# schema.net
KiCad netlist of a schematic drawn in Altium Designer
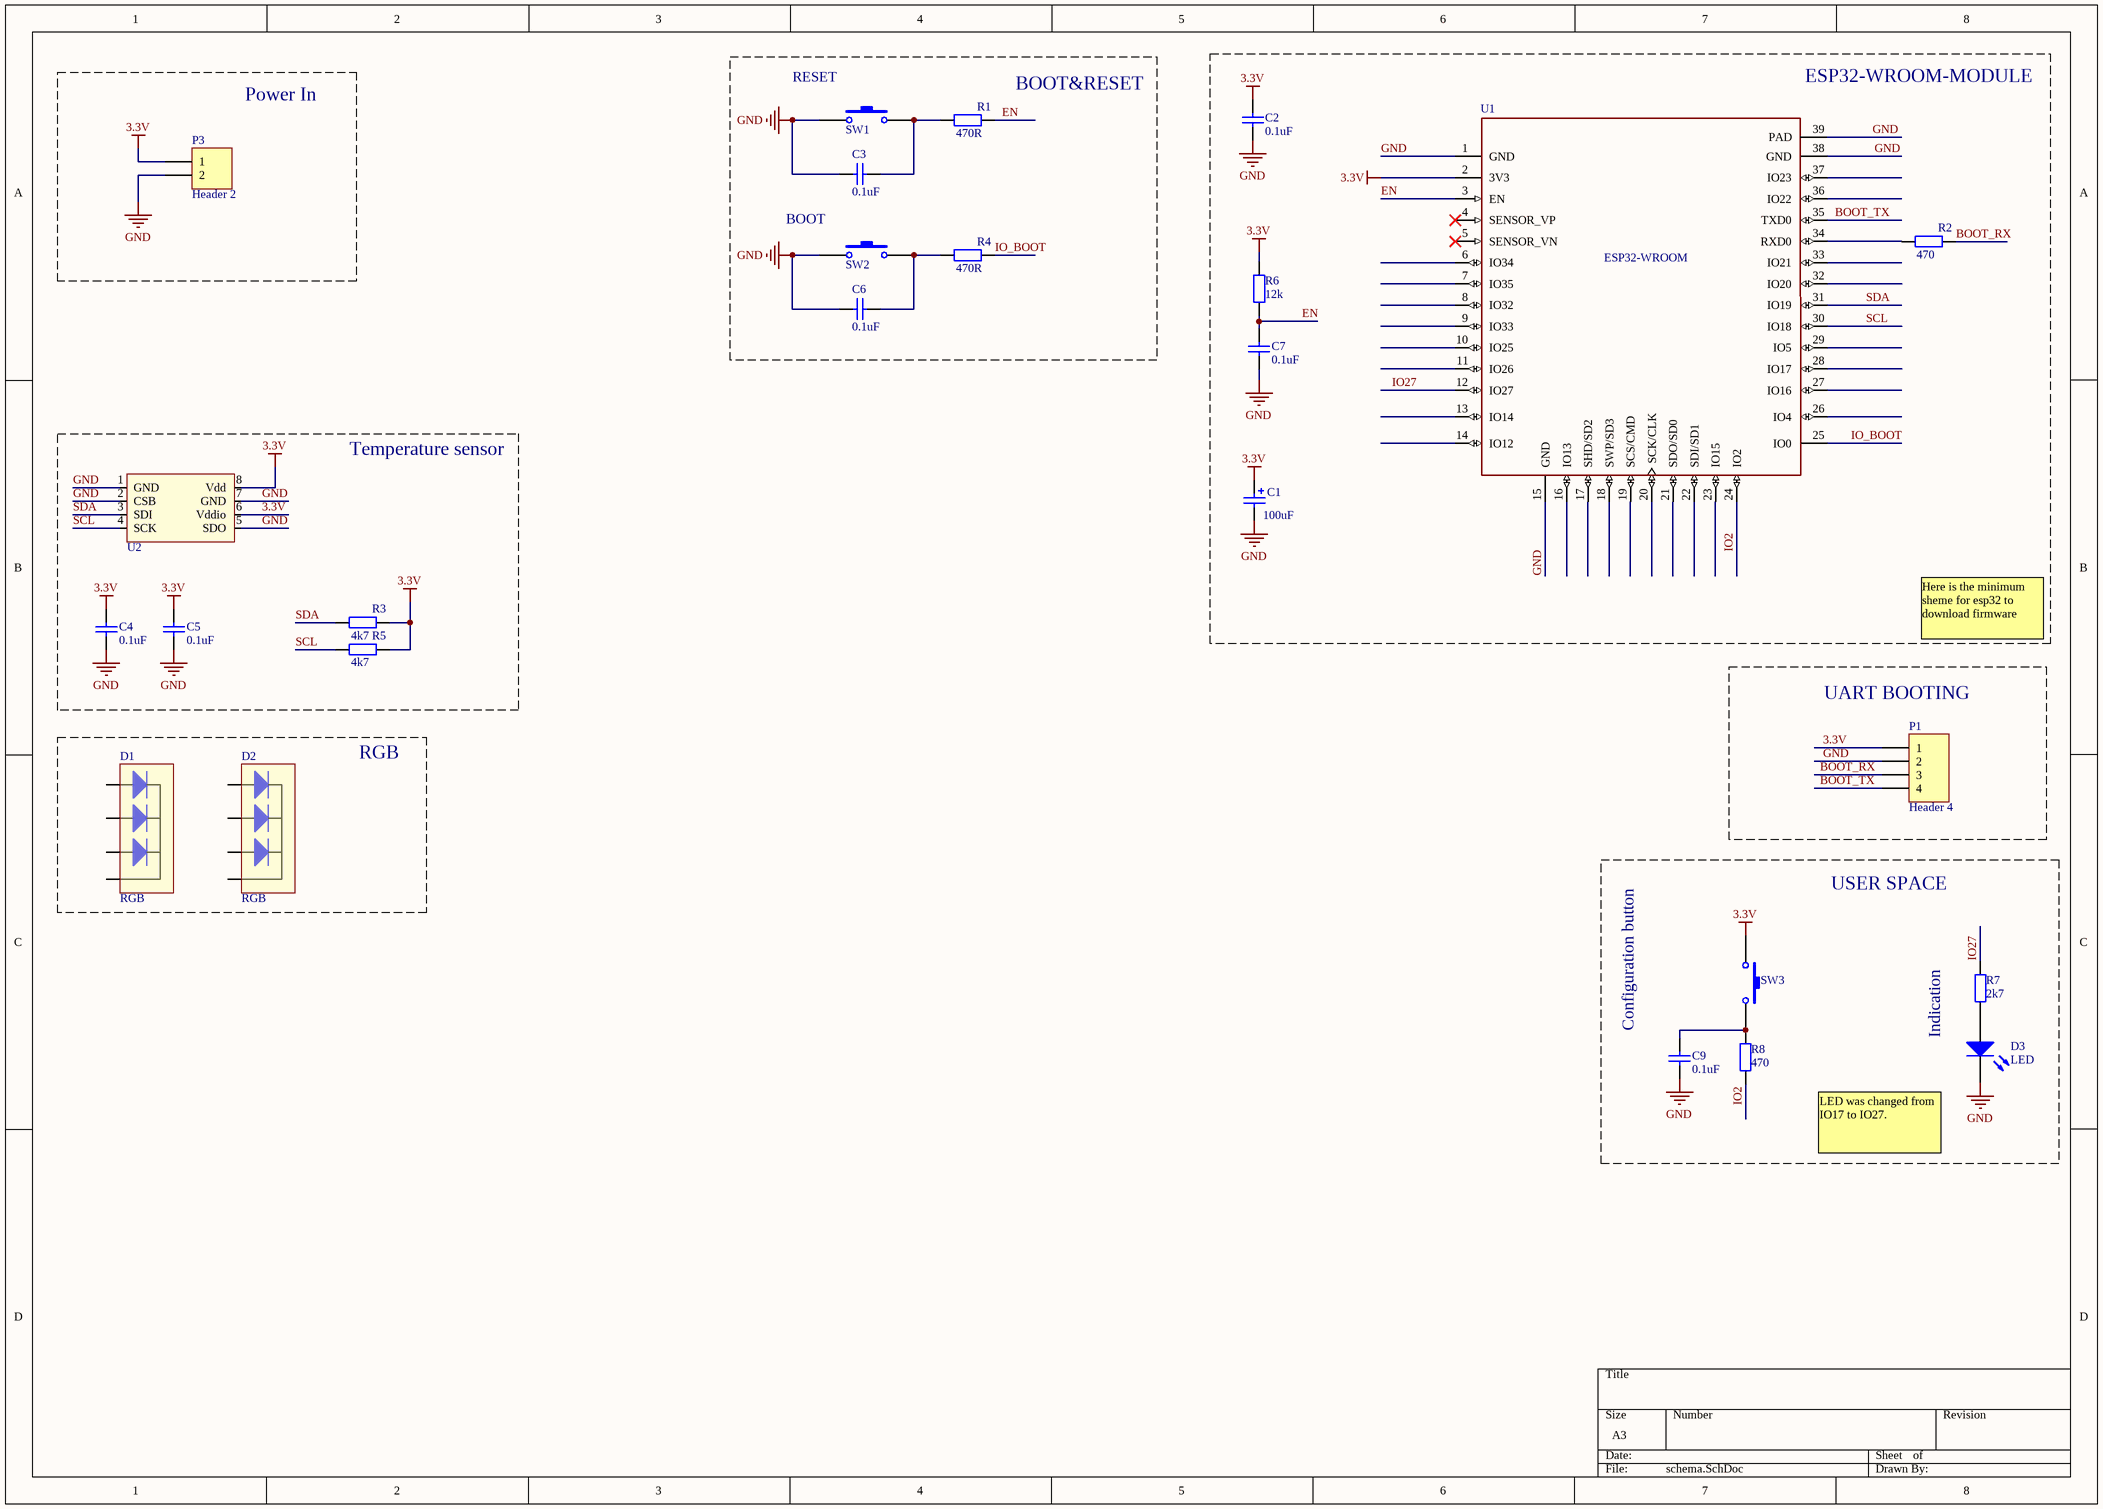
[diagram p0: schema.SchDoc]

(export (version "E")
  (design (tool "Eeschema 10.0.6"))
  (components
    (comp (ref "C1")
      (value "capacitor")
      (footprint "hub_footpr:SMD CAP ALU SIZE D")
      (fields (field (name "VOLTAGE") "100uF"))
      (libsource (lib "hub_comp") (part "Cap_pol"))
    )
    (comp (ref "C2")
      (value "Cap non-polar")
      (footprint "hub_footpr:SMD 0603 CAP")
      (fields (field (name "CAPACITANCE") "0.1uF"))
      (libsource (lib "hub_comp") (part "Cap non-polar"))
    )
    (comp (ref "C3")
      (value "Cap non-polar")
      (footprint "hub_footpr:SMD 0603 CAP")
      (fields (field (name "CAPACITANCE") "0.1uF"))
      (libsource (lib "hub_comp") (part "Cap non-polar"))
    )
    (comp (ref "C4")
      (value "Cap non-polar")
      (footprint "hub_footpr:SMD 0603 CAP")
      (fields (field (name "CAPACITANCE") "0.1uF"))
      (libsource (lib "hub_comp") (part "Cap non-polar"))
    )
    (comp (ref "C5")
      (value "Cap non-polar")
      (footprint "hub_footpr:SMD 0603 CAP")
      (fields (field (name "CAPACITANCE") "0.1uF"))
      (libsource (lib "hub_comp") (part "Cap non-polar"))
    )
    (comp (ref "C6")
      (value "Cap non-polar")
      (footprint "hub_footpr:SMD 0603 CAP")
      (fields (field (name "CAPACITANCE") "0.1uF"))
      (libsource (lib "hub_comp") (part "Cap non-polar"))
    )
    (comp (ref "C7")
      (value "Cap non-polar")
      (footprint "hub_footpr:SMD 0603 CAP")
      (fields (field (name "CAPACITANCE") "0.1uF"))
      (libsource (lib "hub_comp") (part "Cap non-polar"))
    )
    (comp (ref "C9")
      (value "Cap non-polar")
      (footprint "hub_footpr:SMD 0603 CAP")
      (fields (field (name "CAPACITANCE") "0.1uF"))
      (libsource (lib "hub_comp") (part "Cap non-polar"))
    )
    (comp (ref "D1")
      (value "RGB")
      (footprint "hub_footpr:RGB 5mm")
      (libsource (lib "hub_comp") (part "RGB_CC"))
    )
    (comp (ref "D2")
      (value "RGB")
      (footprint "hub_footpr:RGB 5mm")
      (libsource (lib "hub_comp") (part "RGB_CC"))
    )
    (comp (ref "D3")
      (value "LED")
      (footprint "hub_footpr:LED 5mm round")
      (description "Typical BLUE SiC LED")
      (fields (field (name "PUBLISHER") "Altium Limited"))
      (libsource (lib "ESP32_Redesign") (part "LED"))
    )
    (comp (ref "P1")
      (value "Header 4")
      (footprint "HDR1X4")
      (description "Header, 4-Pin")
      (fields (field (name "PUBLISHER") "Altium Limited"))
      (libsource (lib "Miscellaneous Connectors") (part "Header 4"))
    )
    (comp (ref "P3")
      (value "Header 2")
      (footprint "HDR1X2")
      (description "Header, 2-Pin")
      (fields (field (name "PUBLISHER") "Altium Limited"))
      (libsource (lib "Miscellaneous Connectors") (part "Header 2"))
    )
    (comp (ref "R1")
      (value "Resistor")
      (footprint "hub_footpr:SMD 0603 RES")
      (fields (field (name "RES") "470R"))
      (libsource (lib "hub_comp") (part "Resistor"))
    )
    (comp (ref "R2")
      (value "Resistor")
      (footprint "hub_footpr:SMD 0603 RES")
      (fields (field (name "RES") "470"))
      (libsource (lib "hub_comp") (part "Resistor"))
    )
    (comp (ref "R3")
      (value "Resistor")
      (footprint "hub_footpr:SMD 0603 RES")
      (fields (field (name "RES") "4k7"))
      (libsource (lib "hub_comp") (part "Resistor"))
    )
    (comp (ref "R4")
      (value "Resistor")
      (footprint "hub_footpr:SMD 0603 RES")
      (fields (field (name "RES") "470R"))
      (libsource (lib "hub_comp") (part "Resistor"))
    )
    (comp (ref "R5")
      (value "Resistor")
      (footprint "hub_footpr:SMD 0603 RES")
      (fields (field (name "RES") "4k7"))
      (libsource (lib "hub_comp") (part "Resistor"))
    )
    (comp (ref "R6")
      (value "Resistor")
      (footprint "hub_footpr:SMD 0603 RES")
      (fields (field (name "RES") "12k"))
      (libsource (lib "") (part "Resistor_1"))
    )
    (comp (ref "R7")
      (value "Resistor")
      (footprint "hub_footpr:SMD 0603 RES")
      (fields (field (name "RES") "2k7"))
      (libsource (lib "") (part "Resistor_1"))
    )
    (comp (ref "R8")
      (value "Resistor")
      (footprint "hub_footpr:SMD 0603 RES")
      (fields (field (name "RES") "470"))
      (libsource (lib "") (part "Resistor_1"))
    )
    (comp (ref "SW1")
      (value "Button")
      (footprint "hub_footpr:Button reset")
      (libsource (lib "hub_comp") (part "Button"))
    )
    (comp (ref "SW2")
      (value "Button")
      (footprint "Button tact_3x6mm")
      (libsource (lib "hub_comp") (part "Button"))
    )
    (comp (ref "SW3")
      (value "Button")
      (footprint "hub_footpr:Button tact_3x6mm")
      (libsource (lib "hub_comp") (part "Button"))
    )
    (comp (ref "U1")
      (value "ESP32-WROOM")
      (footprint "hub_footpr:ESP_WROOM_32")
      (libsource (lib "hub_comp") (part "ESP32-WROOM"))
    )
    (comp (ref "U2")
      (value "temp sensor")
      (footprint "hub_footpr:LGA")
      (libsource (lib "hub_comp") (part "bme280"))
    )
  )
  (nets
    (net (code "1") (name "/BOOT_RX") (class "Default")
      (node (ref "P1") (pin "3") (pinfunction "3_3") (pintype "passive"))
      (node (ref "R2") (pin "2") (pinfunction "2_2") (pintype "passive"))
    )
    (net (code "2") (name "/BOOT_TX") (class "Default")
      (node (ref "P1") (pin "4") (pinfunction "4_4") (pintype "passive"))
      (node (ref "U1") (pin "35") (pinfunction "TXD0_35") (pintype "bidirectional"))
    )
    (net (code "3") (name "/EN") (class "Default")
      (node (ref "C7") (pin "2") (pinfunction "2_2") (pintype "passive"))
      (node (ref "R1") (pin "2") (pinfunction "2_2") (pintype "passive"))
      (node (ref "R6") (pin "1") (pinfunction "1_1") (pintype "passive"))
      (node (ref "U1") (pin "3") (pinfunction "EN_3") (pintype "input"))
    )
    (net (code "4") (name "/IO2") (class "Default")
      (node (ref "R8") (pin "1") (pinfunction "1_1") (pintype "passive"))
      (node (ref "U1") (pin "24") (pinfunction "IO2_24") (pintype "bidirectional"))
    )
    (net (code "5") (name "/IO27") (class "Default")
      (node (ref "R7") (pin "2") (pinfunction "2_2") (pintype "passive"))
      (node (ref "U1") (pin "12") (pinfunction "IO27_12") (pintype "bidirectional"))
    )
    (net (code "6") (name "/IO_BOOT") (class "Default")
      (node (ref "R4") (pin "2") (pinfunction "2_2") (pintype "passive"))
      (node (ref "U1") (pin "25") (pinfunction "IO0_25") (pintype "passive"))
    )
    (net (code "7") (name "/SCL") (class "Default")
      (node (ref "R5") (pin "1") (pinfunction "1_1") (pintype "passive"))
      (node (ref "U1") (pin "30") (pinfunction "IO18_30") (pintype "bidirectional"))
      (node (ref "U2") (pin "4") (pinfunction "SCK_4") (pintype "passive"))
    )
    (net (code "8") (name "/SDA") (class "Default")
      (node (ref "R3") (pin "1") (pinfunction "1_1") (pintype "passive"))
      (node (ref "U1") (pin "31") (pinfunction "IO19_31") (pintype "bidirectional"))
      (node (ref "U2") (pin "3") (pinfunction "SDI_3") (pintype "passive"))
    )
    (net (code "9") (name "3.3V") (class "Default")
      (node (ref "C1") (pin "1") (pinfunction "A_1") (pintype "passive"))
      (node (ref "C2") (pin "2") (pinfunction "2_2") (pintype "passive"))
      (node (ref "C4") (pin "2") (pinfunction "2_2") (pintype "passive"))
      (node (ref "C5") (pin "2") (pinfunction "2_2") (pintype "passive"))
      (node (ref "P1") (pin "1") (pinfunction "1_1") (pintype "passive"))
      (node (ref "P3") (pin "1") (pinfunction "1_1") (pintype "passive"))
      (node (ref "R3") (pin "2") (pinfunction "2_2") (pintype "passive"))
      (node (ref "R5") (pin "2") (pinfunction "2_2") (pintype "passive"))
      (node (ref "R6") (pin "2") (pinfunction "2_2") (pintype "passive"))
      (node (ref "SW3") (pin "1") (pinfunction "1_1") (pintype "passive"))
      (node (ref "U1") (pin "2") (pinfunction "3V3_2") (pintype "power_in"))
      (node (ref "U2") (pin "6") (pinfunction "Vddio_6") (pintype "passive"))
      (node (ref "U2") (pin "8") (pinfunction "Vdd_8") (pintype "passive"))
    )
    (net (code "10") (name "GND") (class "Default")
      (node (ref "C1") (pin "2") (pinfunction "K_2") (pintype "passive"))
      (node (ref "C2") (pin "1") (pinfunction "1_1") (pintype "passive"))
      (node (ref "C3") (pin "2") (pinfunction "2_2") (pintype "passive"))
      (node (ref "C4") (pin "1") (pinfunction "1_1") (pintype "passive"))
      (node (ref "C5") (pin "1") (pinfunction "1_1") (pintype "passive"))
      (node (ref "C6") (pin "2") (pinfunction "2_2") (pintype "passive"))
      (node (ref "C7") (pin "1") (pinfunction "1_1") (pintype "passive"))
      (node (ref "C9") (pin "1") (pinfunction "1_1") (pintype "passive"))
      (node (ref "D3") (pin "2") (pinfunction "K_2") (pintype "passive"))
      (node (ref "P1") (pin "2") (pinfunction "2_2") (pintype "passive"))
      (node (ref "P3") (pin "2") (pinfunction "2_2") (pintype "passive"))
      (node (ref "SW1") (pin "1") (pinfunction "1_1") (pintype "passive"))
      (node (ref "SW2") (pin "1") (pinfunction "1_1") (pintype "passive"))
      (node (ref "U1") (pin "1") (pinfunction "GND_1") (pintype "power_in"))
      (node (ref "U1") (pin "15") (pinfunction "GND_15") (pintype "power_in"))
      (node (ref "U1") (pin "38") (pinfunction "GND_38") (pintype "power_in"))
      (node (ref "U1") (pin "39") (pinfunction "PAD_39") (pintype "power_in"))
      (node (ref "U2") (pin "1") (pinfunction "GND_1") (pintype "passive"))
      (node (ref "U2") (pin "2") (pinfunction "CSB_2") (pintype "passive"))
      (node (ref "U2") (pin "5") (pinfunction "SDO_5") (pintype "passive"))
      (node (ref "U2") (pin "7") (pinfunction "GND_7") (pintype "passive"))
    )
    (net (code "11") (name "Net-(C3-Pad1)") (class "Default")
      (node (ref "C3") (pin "1") (pinfunction "1_1") (pintype "passive"))
      (node (ref "R1") (pin "1") (pinfunction "1_1") (pintype "passive"))
      (node (ref "SW1") (pin "2") (pinfunction "2_2") (pintype "passive"))
    )
    (net (code "12") (name "Net-(C6-Pad1)") (class "Default")
      (node (ref "C6") (pin "1") (pinfunction "1_1") (pintype "passive"))
      (node (ref "R4") (pin "1") (pinfunction "1_1") (pintype "passive"))
      (node (ref "SW2") (pin "2") (pinfunction "2_2") (pintype "passive"))
    )
    (net (code "13") (name "Net-(C9-Pad2)") (class "Default")
      (node (ref "C9") (pin "2") (pinfunction "2_2") (pintype "passive"))
      (node (ref "R8") (pin "2") (pinfunction "2_2") (pintype "passive"))
      (node (ref "SW3") (pin "2") (pinfunction "2_2") (pintype "passive"))
    )
    (net (code "14") (name "Net-(D3-A)") (class "Default")
      (node (ref "D3") (pin "1") (pinfunction "A_1") (pintype "passive"))
      (node (ref "R7") (pin "1") (pinfunction "1_1") (pintype "passive"))
    )
    (net (code "15") (name "Net-(U1-RXD0)") (class "Default")
      (node (ref "R2") (pin "1") (pinfunction "1_1") (pintype "passive"))
      (node (ref "U1") (pin "34") (pinfunction "RXD0_34") (pintype "bidirectional"))
    )
    (net (code "16") (name "unconnected-(D1-A-Pad1)") (class "Default")
      (node (ref "D1") (pin "1") (pinfunction "A_1") (pintype "passive"))
    )
    (net (code "17") (name "unconnected-(D1-A-Pad4)") (class "Default")
      (node (ref "D1") (pin "4") (pinfunction "A_4") (pintype "passive"))
    )
    (net (code "18") (name "unconnected-(D1-GND-Pad2)") (class "Default")
      (node (ref "D1") (pin "2") (pinfunction "GND_2") (pintype "passive"))
    )
    (net (code "19") (name "unconnected-(D1-Pad3)") (class "Default")
      (node (ref "D1") (pin "3") (pinfunction "3_3") (pintype "passive"))
    )
    (net (code "20") (name "unconnected-(D2-A-Pad1)") (class "Default")
      (node (ref "D2") (pin "1") (pinfunction "A_1") (pintype "passive"))
    )
    (net (code "21") (name "unconnected-(D2-A-Pad4)") (class "Default")
      (node (ref "D2") (pin "4") (pinfunction "A_4") (pintype "passive"))
    )
    (net (code "22") (name "unconnected-(D2-GND-Pad2)") (class "Default")
      (node (ref "D2") (pin "2") (pinfunction "GND_2") (pintype "passive"))
    )
    (net (code "23") (name "unconnected-(D2-Pad3)") (class "Default")
      (node (ref "D2") (pin "3") (pinfunction "3_3") (pintype "passive"))
    )
    (net (code "24") (name "unconnected-(U1-IO4-Pad26)") (class "Default")
      (node (ref "U1") (pin "26") (pinfunction "IO4_26") (pintype "bidirectional"))
    )
    (net (code "25") (name "unconnected-(U1-IO5-Pad29)") (class "Default")
      (node (ref "U1") (pin "29") (pinfunction "IO5_29") (pintype "bidirectional"))
    )
    (net (code "26") (name "unconnected-(U1-IO12-Pad14)") (class "Default")
      (node (ref "U1") (pin "14") (pinfunction "IO12_14") (pintype "bidirectional"))
    )
    (net (code "27") (name "unconnected-(U1-IO13-Pad16)") (class "Default")
      (node (ref "U1") (pin "16") (pinfunction "IO13_16") (pintype "bidirectional"))
    )
    (net (code "28") (name "unconnected-(U1-IO14-Pad13)") (class "Default")
      (node (ref "U1") (pin "13") (pinfunction "IO14_13") (pintype "bidirectional"))
    )
    (net (code "29") (name "unconnected-(U1-IO15-Pad23)") (class "Default")
      (node (ref "U1") (pin "23") (pinfunction "IO15_23") (pintype "bidirectional"))
    )
    (net (code "30") (name "unconnected-(U1-IO16-Pad27)") (class "Default")
      (node (ref "U1") (pin "27") (pinfunction "IO16_27") (pintype "bidirectional"))
    )
    (net (code "31") (name "unconnected-(U1-IO17-Pad28)") (class "Default")
      (node (ref "U1") (pin "28") (pinfunction "IO17_28") (pintype "bidirectional"))
    )
    (net (code "32") (name "unconnected-(U1-IO20-Pad32)") (class "Default")
      (node (ref "U1") (pin "32") (pinfunction "IO20_32") (pintype "bidirectional"))
    )
    (net (code "33") (name "unconnected-(U1-IO21-Pad33)") (class "Default")
      (node (ref "U1") (pin "33") (pinfunction "IO21_33") (pintype "bidirectional"))
    )
    (net (code "34") (name "unconnected-(U1-IO22-Pad36)") (class "Default")
      (node (ref "U1") (pin "36") (pinfunction "IO22_36") (pintype "bidirectional"))
    )
    (net (code "35") (name "unconnected-(U1-IO23-Pad37)") (class "Default")
      (node (ref "U1") (pin "37") (pinfunction "IO23_37") (pintype "bidirectional"))
    )
    (net (code "36") (name "unconnected-(U1-IO25-Pad10)") (class "Default")
      (node (ref "U1") (pin "10") (pinfunction "IO25_10") (pintype "bidirectional"))
    )
    (net (code "37") (name "unconnected-(U1-IO26-Pad11)") (class "Default")
      (node (ref "U1") (pin "11") (pinfunction "IO26_11") (pintype "bidirectional"))
    )
    (net (code "38") (name "unconnected-(U1-IO32-Pad8)") (class "Default")
      (node (ref "U1") (pin "8") (pinfunction "IO32_8") (pintype "bidirectional"))
    )
    (net (code "39") (name "unconnected-(U1-IO33-Pad9)") (class "Default")
      (node (ref "U1") (pin "9") (pinfunction "IO33_9") (pintype "bidirectional"))
    )
    (net (code "40") (name "unconnected-(U1-IO34-Pad6)") (class "Default")
      (node (ref "U1") (pin "6") (pinfunction "IO34_6") (pintype "bidirectional"))
    )
    (net (code "41") (name "unconnected-(U1-IO35-Pad7)") (class "Default")
      (node (ref "U1") (pin "7") (pinfunction "IO35_7") (pintype "bidirectional"))
    )
    (net (code "42") (name "unconnected-(U1-SCK{slash}CLK-Pad20)") (class "Default")
      (node (ref "U1") (pin "20") (pinfunction "SCK/CLK_20") (pintype "bidirectional"))
    )
    (net (code "43") (name "unconnected-(U1-SCS{slash}CMD-Pad19)") (class "Default")
      (node (ref "U1") (pin "19") (pinfunction "SCS/CMD_19") (pintype "bidirectional"))
    )
    (net (code "44") (name "unconnected-(U1-SDI{slash}SD1-Pad22)") (class "Default")
      (node (ref "U1") (pin "22") (pinfunction "SDI/SD1_22") (pintype "bidirectional"))
    )
    (net (code "45") (name "unconnected-(U1-SDO{slash}SD0-Pad21)") (class "Default")
      (node (ref "U1") (pin "21") (pinfunction "SDO/SD0_21") (pintype "bidirectional"))
    )
    (net (code "46") (name "unconnected-(U1-SENSOR_VN-Pad5)") (class "Default")
      (node (ref "U1") (pin "5") (pinfunction "SENSOR_VN_5") (pintype "input+no_connect"))
    )
    (net (code "47") (name "unconnected-(U1-SENSOR_VP-Pad4)") (class "Default")
      (node (ref "U1") (pin "4") (pinfunction "SENSOR_VP_4") (pintype "input+no_connect"))
    )
    (net (code "48") (name "unconnected-(U1-SHD{slash}SD2-Pad17)") (class "Default")
      (node (ref "U1") (pin "17") (pinfunction "SHD/SD2_17") (pintype "bidirectional"))
    )
    (net (code "49") (name "unconnected-(U1-SWP{slash}SD3-Pad18)") (class "Default")
      (node (ref "U1") (pin "18") (pinfunction "SWP/SD3_18") (pintype "bidirectional"))
    )
  )
)
